# PoE.net
KiCad netlist of a schematic drawn in Altium Designer
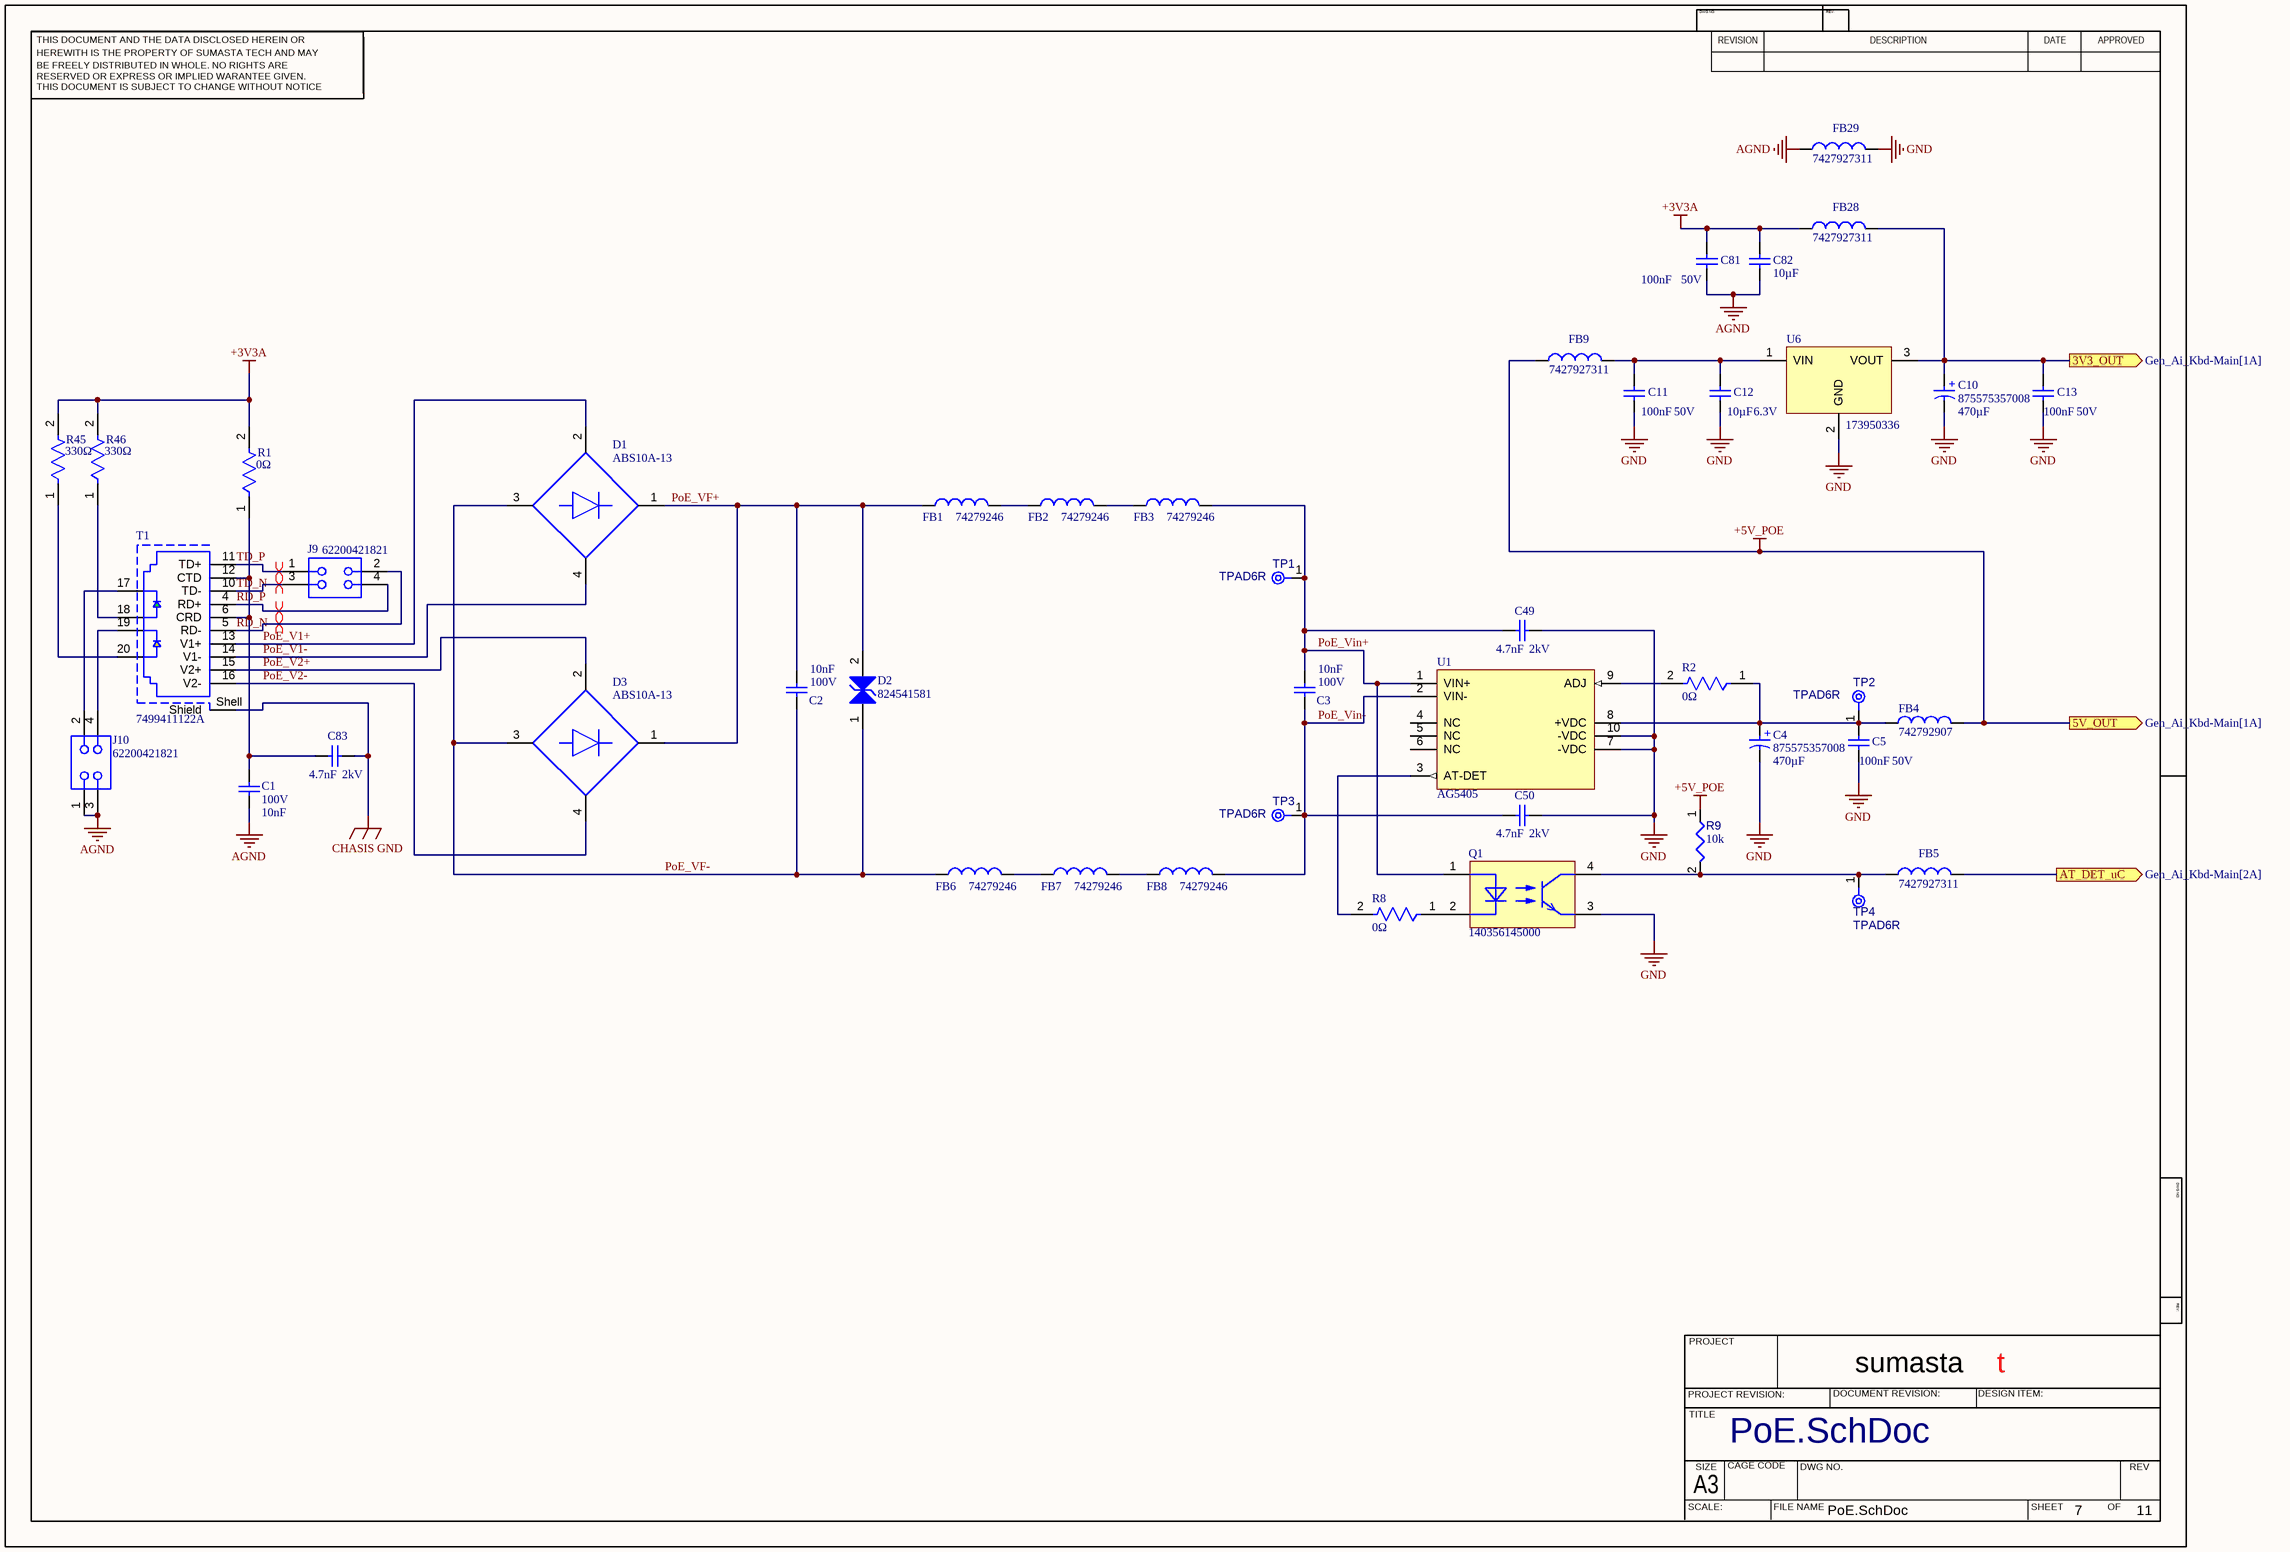
[diagram p0: PoE.SchDoc]

(export (version "E")
  (design (tool "Eeschema 10.0.6"))
  (components
    (comp (ref "C1")
      (value "885012206114")
      (footprint "WCAP-CSGP_0603_L1.6W0.8H0.8_Reflow")
      (description "WCAP-CSGP Multilayer Ceramic Chip Capacitor, General Purpose, size 0603, X7R, 10nF, 100VDC")
      (fields
        (field (name "RATED VOLTAGE (DC)") "100V")
        (field (name "CAPACITANCE") "10nF")
        (field (name "MANUFACTURER") "Wurth Elektronik")
      )
      (libsource (lib "Test365") (part "885012209047R"))
    )
    (comp (ref "C2")
      (value "885012008079")
      (footprint "WCAP-CSGP_1206_L3.2W1.6H1.25")
      (description "WCAP-CSGP Multilayer Ceramic Chip Capacitor, General Purpose, size 1206, NP0, 10nF, 100VDC")
      (fields
        (field (name "RATED VOLTAGE (DC)") "100V")
        (field (name "CAPACITANCE") "10nF")
        (field (name "MANUFACTURER") "Wurth Elektronik")
      )
      (libsource (lib "Test365") (part "885012209047R"))
    )
    (comp (ref "C3")
      (value "885012008079")
      (footprint "WCAP-CSGP_1206_L3.2W1.6H1.25")
      (description "WCAP-CSGP Multilayer Ceramic Chip Capacitor, General Purpose, size 1206, NP0, 10nF, 100VDC")
      (fields
        (field (name "RATED VOLTAGE (DC)") "100V")
        (field (name "CAPACITANCE") "10nF")
        (field (name "MANUFACTURER") "Wurth Elektronik")
      )
      (libsource (lib "Test365") (part "885012209047R"))
    )
    (comp (ref "C4")
      (value "875575357008")
      (footprint "WCAP-HSG5_D10H10.5")
      (description "875575357008 Cap, 470Uf, 16V, Alu Elec, Hybrid, Smd Rohs Compliant: Yes")
      (fields (field (name "CAPACITANCE") "470µF"))
      (libsource (lib "Altium Content Vault") (part "Capacitor_Polarized"))
    )
    (comp (ref "C5")
      (value "885012206095")
      (footprint "WCAP-CSGP_0603_L1.6W0.8H0.8_Reflow")
      (description "WCAP-CSGP Multilayer Ceramic Chip Capacitor, General Purpose, size 0603, X7R, 100nF, 50VDC")
      (fields
        (field (name "CAPACITANCE") "100nF")
        (field (name "MANUFACTURER") "Wurth Elektronik")
        (field (name "RATED VOLTAGE (DC)") "50V")
      )
      (libsource (lib "Test365") (part "885012209047R"))
    )
    (comp (ref "C10")
      (value "875575357008")
      (footprint "WCAP-HSG5_D10H10.5")
      (description "875575357008 Cap, 470Uf, 16V, Alu Elec, Hybrid, Smd Rohs Compliant: Yes")
      (fields (field (name "CAPACITANCE") "470µF"))
      (libsource (lib "Altium Content Vault") (part "Capacitor_Polarized"))
    )
    (comp (ref "C11")
      (value "885012206095")
      (footprint "WCAP-CSGP_0603_L1.6W0.8H0.8_Reflow")
      (description "WCAP-CSGP Multilayer Ceramic Chip Capacitor, General Purpose, size 0603, X7R, 100nF, 50VDC")
      (fields
        (field (name "CAPACITANCE") "100nF")
        (field (name "MANUFACTURER") "Wurth Elektronik")
        (field (name "RATED VOLTAGE (DC)") "50V")
      )
      (libsource (lib "Test365") (part "885012209047R"))
    )
    (comp (ref "C12")
      (value "885012106006")
      (footprint "WCAP-CSGP_0603_L1.6W0.8H0.8_Reflow")
      (description "WCAP-CSGP Multilayer Ceramic Chip Capacitor, General Purpose, size 0603, X5R, 10µF, 6.3VDC")
      (fields
        (field (name "RATED VOLTAGE (DC)") "6.3V")
        (field (name "MANUFACTURER") "Wurth Elektronik")
        (field (name "CAPACITANCE") "10µF")
      )
      (libsource (lib "Test365") (part "885012209047R"))
    )
    (comp (ref "C13")
      (value "885012206095")
      (footprint "WCAP-CSGP_0603_L1.6W0.8H0.8_Reflow")
      (description "WCAP-CSGP Multilayer Ceramic Chip Capacitor, General Purpose, size 0603, X7R, 100nF, 50VDC")
      (fields
        (field (name "CAPACITANCE") "100nF")
        (field (name "MANUFACTURER") "Wurth Elektronik")
        (field (name "RATED VOLTAGE (DC)") "50V")
      )
      (libsource (lib "Test365") (part "885012209047R"))
    )
    (comp (ref "C49")
      (value "885342211008")
      (footprint "WCAP-CSMH_1812_L4.5W3.2H2")
      (description "885342211008 4700PF 2000V X7R 1812 10% - Multilayer Ceramic Capacitors")
      (fields (field (name "VOLTAGE RATING (DC)") "2kV") (field (name "CAPACITANCE") "4.7nF"))
      (libsource (lib "Altium Content Vault") (part "Capacitor_Non-Polarized"))
    )
    (comp (ref "C50")
      (value "885342211008")
      (footprint "WCAP-CSMH_1812_L4.5W3.2H2")
      (description "885342211008 4700PF 2000V X7R 1812 10% - Multilayer Ceramic Capacitors")
      (fields (field (name "VOLTAGE RATING (DC)") "2kV") (field (name "CAPACITANCE") "4.7nF"))
      (libsource (lib "Altium Content Vault") (part "Capacitor_Non-Polarized"))
    )
    (comp (ref "C81")
      (value "885012206095")
      (footprint "WCAP-CSGP_0603_L1.6W0.8H0.8_Reflow")
      (description "WCAP-CSGP Multilayer Ceramic Chip Capacitor, General Purpose, size 0603, X7R, 100nF, 50VDC")
      (fields
        (field (name "CAPACITANCE") "100nF")
        (field (name "MANUFACTURER") "Wurth Elektronik")
        (field (name "RATED VOLTAGE (DC)") "50V")
      )
      (libsource (lib "Test365") (part "885012209047R"))
    )
    (comp (ref "C82")
      (value "885012106006")
      (footprint "WCAP-CSGP_0603_L1.6W0.8H0.8_Reflow")
      (description "WCAP-CSGP Multilayer Ceramic Chip Capacitor, General Purpose, size 0603, X5R, 10µF, 6.3VDC")
      (fields (field (name "MANUFACTURER") "Wurth Elektronik") (field (name "CAPACITANCE") "10µF"))
      (libsource (lib "Test365") (part "885012209047R"))
    )
    (comp (ref "C83")
      (value "885342211008")
      (footprint "WCAP-CSMH_1812_L4.5W3.2H2")
      (description "885342211008 4700PF 2000V X7R 1812 10% - Multilayer Ceramic Capacitors")
      (fields (field (name "VOLTAGE RATING (DC)") "2kV") (field (name "CAPACITANCE") "4.7nF"))
      (libsource (lib "Altium Content Vault") (part "Capacitor_Non-Polarized"))
    )
    (comp (ref "D1")
      (value "ABS10A-13")
      (footprint "FP-SOPA-4-MFG")
      (description "BRIDGE RECT 1PHASE 1KV 1A 4SOPA")
      (libsource (lib "Altium Content Vault") (part "95261e4f58a5ffcdc7f7244183d0b96"))
    )
    (comp (ref "D2")
      (value "824541581")
      (footprint "WE-TVSP_DO-214AB_Bidirectional")
      (description "824541581 TVS diode [Würth Elektronik] 824541581 TVS diode")
      (libsource (lib "Altium Content Vault") (part "WE-TVSP_Bidirectional"))
    )
    (comp (ref "D3")
      (value "ABS10A-13")
      (footprint "FP-SOPA-4-MFG")
      (description "BRIDGE RECT 1PHASE 1KV 1A 4SOPA")
      (libsource (lib "Altium Content Vault") (part "95261e4f58a5ffcdc7f7244183d0b96"))
    )
    (comp (ref "FB1")
      (value "74279246")
      (footprint "WE-CBF_1806_L4.5W1.6H1.6_HS/WB")
      (description "WE-CBF SMT EMI Suppression Ferrite Bead, size 1806, 1000Ohm, 1.5A")
      (fields (field (name "MANUFACTURER") "Wurth Elektronik"))
      (libsource (lib "Test365") (part "7427928801"))
    )
    (comp (ref "FB2")
      (value "74279246")
      (footprint "WE-CBF_1806_L4.5W1.6H1.6_HS/WB")
      (description "WE-CBF SMT EMI Suppression Ferrite Bead, size 1806, 1000Ohm, 1.5A")
      (fields (field (name "MANUFACTURER") "Wurth Elektronik"))
      (libsource (lib "Test365") (part "7427928801"))
    )
    (comp (ref "FB3")
      (value "74279246")
      (footprint "WE-CBF_1806_L4.5W1.6H1.6_HS/WB")
      (description "WE-CBF SMT EMI Suppression Ferrite Bead, size 1806, 1000Ohm, 1.5A")
      (fields (field (name "MANUFACTURER") "Wurth Elektronik"))
      (libsource (lib "Test365") (part "7427928801"))
    )
    (comp (ref "FB4")
      (value "742792907")
      (footprint "WE-PF_1280")
      (fields (field (name "TOLERANCE") "25%"))
      (libsource (lib "Altium Content Vault") (part "Ferrite"))
    )
    (comp (ref "FB5")
      (value "7427927311")
      (footprint "WE-CBF_0402_L1W0.5H0.5_HC")
      (fields (field (name "TOLERANCE") "25%"))
      (libsource (lib "Altium Content Vault") (part "Ferrite"))
    )
    (comp (ref "FB6")
      (value "74279246")
      (footprint "WE-CBF_1806_L4.5W1.6H1.6_HS/WB")
      (description "WE-CBF SMT EMI Suppression Ferrite Bead, size 1806, 1000Ohm, 1.5A")
      (fields (field (name "MANUFACTURER") "Wurth Elektronik"))
      (libsource (lib "Test365") (part "7427928801"))
    )
    (comp (ref "FB7")
      (value "74279246")
      (footprint "WE-CBF_1806_L4.5W1.6H1.6_HS/WB")
      (description "WE-CBF SMT EMI Suppression Ferrite Bead, size 1806, 1000Ohm, 1.5A")
      (fields (field (name "MANUFACTURER") "Wurth Elektronik"))
      (libsource (lib "Test365") (part "7427928801"))
    )
    (comp (ref "FB8")
      (value "74279246")
      (footprint "WE-CBF_1806_L4.5W1.6H1.6_HS/WB")
      (description "WE-CBF SMT EMI Suppression Ferrite Bead, size 1806, 1000Ohm, 1.5A")
      (fields (field (name "MANUFACTURER") "Wurth Elektronik"))
      (libsource (lib "Test365") (part "7427928801"))
    )
    (comp (ref "FB9")
      (value "7427927311")
      (footprint "WE-CBF_0402_L1W0.5H0.5_HC")
      (fields (field (name "TOLERANCE") "25%"))
      (libsource (lib "Altium Content Vault") (part "Ferrite"))
    )
    (comp (ref "FB28")
      (value "7427927311")
      (footprint "WE-CBF_0402_L1W0.5H0.5_HC")
      (fields (field (name "TOLERANCE") "25%"))
      (libsource (lib "Altium Content Vault") (part "Ferrite"))
    )
    (comp (ref "FB29")
      (value "7427927311")
      (footprint "WE-CBF_0402_L1W0.5H0.5_HC")
      (fields (field (name "TOLERANCE") "25%"))
      (libsource (lib "Altium Content Vault") (part "Ferrite"))
    )
    (comp (ref "J9")
      (value "62200421821")
      (footprint "62200421821")
      (libsource (lib "Altium Content Vault") (part "Header_Female_2R_04P"))
    )
    (comp (ref "J10")
      (value "62200421821")
      (footprint "62200421821")
      (libsource (lib "Altium Content Vault") (part "Header_Female_2R_04P"))
    )
    (comp (ref "Q1")
      (value "140356145000")
      (footprint "WL-OCPT_SOP4")
      (description "140356145000 Optocoupler, Transistor, 80V, Sop-4 Rohs Compliant: Yes")
      (libsource (lib "Altium Content Vault") (part "Optocoupler Phototransistor_DC_1 Channel"))
    )
    (comp (ref "R1")
      (value "0Ω")
      (footprint "FP-RC0603-MFG")
      (description "RES SMD 0 OHM JUMPER 1/10W 0603")
      (fields
        (field (name "TOLERANCE") "1%")
        (field (name "OCTOPART") "https://octopart.com/rc0603fr-070rl-yageo-1180803")
      )
      (libsource (lib "Altium Content Vault") (part "1029c3af85768c4190bb7ad29bc67b5"))
    )
    (comp (ref "R2")
      (value "0Ω")
      (footprint "FP-RC0603-MFG")
      (description "RES SMD 0 OHM JUMPER 1/10W 0603")
      (fields
        (field (name "TOLERANCE") "1%")
        (field (name "OCTOPART") "https://octopart.com/rc0603fr-070rl-yageo-1180803")
      )
      (libsource (lib "Altium Content Vault") (part "1029c3af85768c4190bb7ad29bc67b5"))
    )
    (comp (ref "R8")
      (value "0Ω")
      (footprint "FP-RC0603-MFG")
      (description "RES SMD 0 OHM JUMPER 1/10W 0603")
      (fields
        (field (name "TOLERANCE") "1%")
        (field (name "OCTOPART") "https://octopart.com/rc0603fr-070rl-yageo-1180803")
      )
      (libsource (lib "Altium Content Vault") (part "1029c3af85768c4190bb7ad29bc67b5"))
    )
    (comp (ref "R9")
      (value "10k")
      (footprint "RESC1608X55X25ML10T15")
      (description "Chip Resistor, 10 KOhm, +/- 1%, 01 W, -55 to 155 degC, 0603 (1608 Metric)")
      (fields (field (name "POWER") "100mW") (field (name "TOLERANCE") "1%"))
      (libsource (lib "Test365") (part "RES-2"))
    )
    (comp (ref "R45")
      (value "330Ω")
      (footprint "FP-RC0603-MFG")
      (description "RES SMD 0 OHM JUMPER 1/10W 0603")
      (fields
        (field (name "TOLERANCE") "1%")
        (field (name "OCTOPART") "https://octopart.com/rc0603fr-070rl-yageo-1180803")
      )
      (libsource (lib "Altium Content Vault") (part "1029c3af85768c4190bb7ad29bc67b5"))
    )
    (comp (ref "R46")
      (value "330Ω")
      (footprint "FP-RC0603-MFG")
      (description "RES SMD 0 OHM JUMPER 1/10W 0603")
      (fields
        (field (name "TOLERANCE") "1%")
        (field (name "OCTOPART") "https://octopart.com/rc0603fr-070rl-yageo-1180803")
      )
      (libsource (lib "Altium Content Vault") (part "1029c3af85768c4190bb7ad29bc67b5"))
    )
    (comp (ref "T1")
      (value "7499411122A")
      (footprint "7499411122A")
      (description "7499411122A Rj45 Conn, R/A Jack, 8P8C, 1Port, Th Rohs Compliant: Yes")
      (libsource (lib "Altium Content Vault") (part "7499411122A"))
    )
    (comp (ref "TP1")
      (value "TPAD6R")
      (footprint "TP06R")
      (description "0.6mm round")
      (libsource (lib "Test365") (part "CMP-001-0001-4"))
    )
    (comp (ref "TP2")
      (value "TPAD6R")
      (footprint "TP06R")
      (description "0.6mm round")
      (libsource (lib "Test365") (part "CMP-001-0001-4"))
    )
    (comp (ref "TP3")
      (value "TPAD6R")
      (footprint "TP06R")
      (description "0.6mm round")
      (libsource (lib "Test365") (part "CMP-001-0001-4"))
    )
    (comp (ref "TP4")
      (value "TPAD6R")
      (footprint "TP06R")
      (description "0.6mm round")
      (libsource (lib "Test365") (part "CMP-001-0001-4"))
    )
    (comp (ref "U1")
      (value "AG5405")
      (footprint "AG540X")
      (description "PoE Module 802.3at")
      (libsource (lib "Test365") (part "SYM_AG540X"))
    )
    (comp (ref "U6")
      (value "173950336")
      (footprint "WPME-FDSM_SIP-3_L11.6W7.55H10.16")
      (description "173950336 WPME-FDSM Fixed Step Down Regulator Module")
      (libsource (lib "Altium Content Vault") (part "SIP-3_WPME-FDSM"))
    )
  )
  (nets
    (net (code "1") (name "+3V3A") (class "Default")
      (node (ref "C81") (pin "2") (pinfunction "2_2") (pintype "passive"))
      (node (ref "C82") (pin "2") (pinfunction "2_2") (pintype "passive"))
      (node (ref "FB28") (pin "1") (pinfunction "1_1") (pintype "passive"))
      (node (ref "R1") (pin "2") (pinfunction "2_2") (pintype "passive"))
      (node (ref "R45") (pin "2") (pinfunction "2_2") (pintype "passive"))
      (node (ref "R46") (pin "2") (pinfunction "2_2") (pintype "passive"))
    )
    (net (code "2") (name "+5V_POE") (class "Default")
      (node (ref "FB4") (pin "2") (pinfunction "2_2") (pintype "passive"))
      (node (ref "FB9") (pin "1") (pinfunction "1_1") (pintype "passive"))
      (node (ref "R9") (pin "1") (pinfunction "1_1") (pintype "passive"))
    )
    (net (code "3") (name "/3V3_OUT") (class "Default")
      (node (ref "C10") (pin "1") (pinfunction "P_1") (pintype "passive"))
      (node (ref "C13") (pin "2") (pinfunction "2_2") (pintype "passive"))
      (node (ref "FB28") (pin "2") (pinfunction "2_2") (pintype "passive"))
      (node (ref "U6") (pin "3") (pinfunction "VOUT_3") (pintype "passive"))
    )
    (net (code "4") (name "/AT_DET_uC") (class "Default")
      (node (ref "FB5") (pin "2") (pinfunction "2_2") (pintype "passive"))
    )
    (net (code "5") (name "/PoE_V1+") (class "Default")
      (node (ref "D1") (pin "2") (pinfunction "1_~_2") (pintype "passive"))
      (node (ref "T1") (pin "13") (pinfunction "V1+_13") (pintype "passive"))
    )
    (net (code "6") (name "/PoE_V1-") (class "Default")
      (node (ref "D1") (pin "4") (pinfunction "2_~_4") (pintype "passive"))
      (node (ref "T1") (pin "14") (pinfunction "V1-_14") (pintype "passive"))
    )
    (net (code "7") (name "/PoE_V2+") (class "Default")
      (node (ref "D3") (pin "2") (pinfunction "1_~_2") (pintype "passive"))
      (node (ref "T1") (pin "15") (pinfunction "V2+_15") (pintype "passive"))
    )
    (net (code "8") (name "/PoE_V2-") (class "Default")
      (node (ref "D3") (pin "4") (pinfunction "2_~_4") (pintype "passive"))
      (node (ref "T1") (pin "16") (pinfunction "V2-_16") (pintype "passive"))
    )
    (net (code "9") (name "/PoE_VF+") (class "Default")
      (node (ref "C2") (pin "2") (pinfunction "2_2") (pintype "passive"))
      (node (ref "D1") (pin "1") (pinfunction "+_1") (pintype "passive"))
      (node (ref "D2") (pin "2") (pinfunction "2_2") (pintype "passive"))
      (node (ref "D3") (pin "1") (pinfunction "+_1") (pintype "passive"))
      (node (ref "FB1") (pin "1") (pinfunction "1_1") (pintype "passive"))
    )
    (net (code "10") (name "/PoE_VF-") (class "Default")
      (node (ref "C2") (pin "1") (pinfunction "1_1") (pintype "passive"))
      (node (ref "D1") (pin "3") (pinfunction "-_3") (pintype "passive"))
      (node (ref "D2") (pin "1") (pinfunction "1_1") (pintype "passive"))
      (node (ref "D3") (pin "3") (pinfunction "-_3") (pintype "passive"))
      (node (ref "FB6") (pin "1") (pinfunction "1_1") (pintype "passive"))
    )
    (net (code "11") (name "/PoE_Vin+") (class "Default")
      (node (ref "C3") (pin "2") (pinfunction "2_2") (pintype "passive"))
      (node (ref "C49") (pin "1") (pinfunction "1_1") (pintype "passive"))
      (node (ref "FB3") (pin "2") (pinfunction "2_2") (pintype "passive"))
      (node (ref "Q1") (pin "1") (pinfunction "Anode_1") (pintype "passive"))
      (node (ref "TP1") (pin "1") (pinfunction "TP_1") (pintype "passive"))
      (node (ref "U1") (pin "1") (pinfunction "VIN+_1") (pintype "power_in"))
    )
    (net (code "12") (name "/PoE_Vin-") (class "Default")
      (node (ref "C3") (pin "1") (pinfunction "1_1") (pintype "passive"))
      (node (ref "C50") (pin "1") (pinfunction "1_1") (pintype "passive"))
      (node (ref "FB8") (pin "2") (pinfunction "2_2") (pintype "passive"))
      (node (ref "TP3") (pin "1") (pinfunction "TP_1") (pintype "passive"))
      (node (ref "U1") (pin "2") (pinfunction "VIN-_2") (pintype "power_in"))
    )
    (net (code "13") (name "/RD_N") (class "Default")
      (node (ref "J9") (pin "2") (pinfunction "2_2") (pintype "passive"))
      (node (ref "T1") (pin "5") (pinfunction "RD-_5") (pintype "passive"))
    )
    (net (code "14") (name "/RD_P") (class "Default")
      (node (ref "J9") (pin "4") (pinfunction "4_4") (pintype "passive"))
      (node (ref "T1") (pin "4") (pinfunction "RD+_4") (pintype "passive"))
    )
    (net (code "15") (name "/TD_N") (class "Default")
      (node (ref "J9") (pin "3") (pinfunction "3_3") (pintype "passive"))
      (node (ref "T1") (pin "10") (pinfunction "TD-_10") (pintype "passive"))
    )
    (net (code "16") (name "/TD_P") (class "Default")
      (node (ref "J9") (pin "1") (pinfunction "1_1") (pintype "passive"))
      (node (ref "T1") (pin "11") (pinfunction "TD+_11") (pintype "passive"))
    )
    (net (code "17") (name "AGND") (class "Default")
      (node (ref "C1") (pin "2") (pinfunction "2_2") (pintype "passive"))
      (node (ref "C81") (pin "1") (pinfunction "1_1") (pintype "passive"))
      (node (ref "C82") (pin "1") (pinfunction "1_1") (pintype "passive"))
      (node (ref "FB29") (pin "1") (pinfunction "1_1") (pintype "passive"))
      (node (ref "J10") (pin "1") (pinfunction "1_1") (pintype "passive"))
      (node (ref "J10") (pin "3") (pinfunction "3_3") (pintype "passive"))
    )
    (net (code "18") (name "CHASIS GND") (class "Default")
      (node (ref "C83") (pin "2") (pinfunction "2_2") (pintype "passive"))
      (node (ref "T1") (pin "Shell") (pinfunction "Shield_Shell") (pintype "passive"))
    )
    (net (code "19") (name "GND") (class "Default")
      (node (ref "C10") (pin "2") (pinfunction "N_2") (pintype "passive"))
      (node (ref "C11") (pin "1") (pinfunction "1_1") (pintype "passive"))
      (node (ref "C12") (pin "1") (pinfunction "1_1") (pintype "passive"))
      (node (ref "C13") (pin "1") (pinfunction "1_1") (pintype "passive"))
      (node (ref "C4") (pin "2") (pinfunction "N_2") (pintype "passive"))
      (node (ref "C49") (pin "2") (pinfunction "2_2") (pintype "passive"))
      (node (ref "C5") (pin "1") (pinfunction "1_1") (pintype "passive"))
      (node (ref "C50") (pin "2") (pinfunction "2_2") (pintype "passive"))
      (node (ref "FB29") (pin "2") (pinfunction "2_2") (pintype "passive"))
      (node (ref "Q1") (pin "3") (pinfunction "Emitter_3") (pintype "passive"))
      (node (ref "U1") (pin "10") (pinfunction "-VDC_10") (pintype "power_in"))
      (node (ref "U1") (pin "7") (pinfunction "-VDC_7") (pintype "power_in"))
      (node (ref "U6") (pin "2") (pinfunction "GND_2") (pintype "passive"))
    )
    (net (code "20") (name "Net-(C4-P)") (class "Default")
      (node (ref "C4") (pin "1") (pinfunction "P_1") (pintype "passive"))
      (node (ref "C5") (pin "2") (pinfunction "2_2") (pintype "passive"))
      (node (ref "FB4") (pin "1") (pinfunction "1_1") (pintype "passive"))
      (node (ref "R2") (pin "1") (pinfunction "1_1") (pintype "passive"))
      (node (ref "TP2") (pin "1") (pinfunction "TP_1") (pintype "passive"))
      (node (ref "U1") (pin "8") (pinfunction "+VDC_8") (pintype "power_in"))
    )
    (net (code "21") (name "Net-(FB1-Pad2)") (class "Default")
      (node (ref "FB1") (pin "2") (pinfunction "2_2") (pintype "passive"))
      (node (ref "FB2") (pin "1") (pinfunction "1_1") (pintype "passive"))
    )
    (net (code "22") (name "Net-(FB2-Pad2)") (class "Default")
      (node (ref "FB2") (pin "2") (pinfunction "2_2") (pintype "passive"))
      (node (ref "FB3") (pin "1") (pinfunction "1_1") (pintype "passive"))
    )
    (net (code "23") (name "Net-(FB6-Pad2)") (class "Default")
      (node (ref "FB6") (pin "2") (pinfunction "2_2") (pintype "passive"))
      (node (ref "FB7") (pin "1") (pinfunction "1_1") (pintype "passive"))
    )
    (net (code "24") (name "Net-(FB7-Pad2)") (class "Default")
      (node (ref "FB7") (pin "2") (pinfunction "2_2") (pintype "passive"))
      (node (ref "FB8") (pin "1") (pinfunction "1_1") (pintype "passive"))
    )
    (net (code "25") (name "Net-(J10-Pad2)") (class "Default")
      (node (ref "J10") (pin "2") (pinfunction "2_2") (pintype "passive"))
      (node (ref "T1") (pin "17") (pinfunction "17_17") (pintype "passive"))
    )
    (net (code "26") (name "Net-(J10-Pad4)") (class "Default")
      (node (ref "J10") (pin "4") (pinfunction "4_4") (pintype "passive"))
      (node (ref "T1") (pin "19") (pinfunction "19_19") (pintype "passive"))
    )
    (net (code "27") (name "Net-(Q1-Cathode)") (class "Default")
      (node (ref "Q1") (pin "2") (pinfunction "Cathode_2") (pintype "passive"))
      (node (ref "R8") (pin "1") (pinfunction "1_1") (pintype "passive"))
    )
    (net (code "28") (name "Net-(Q1-Collector)") (class "Default")
      (node (ref "FB5") (pin "1") (pinfunction "1_1") (pintype "passive"))
      (node (ref "Q1") (pin "4") (pinfunction "Collector_4") (pintype "passive"))
      (node (ref "R9") (pin "2") (pinfunction "2_2") (pintype "passive"))
      (node (ref "TP4") (pin "1") (pinfunction "TP_1") (pintype "passive"))
    )
    (net (code "29") (name "Net-(R45-Pad1)") (class "Default")
      (node (ref "R45") (pin "1") (pinfunction "1_1") (pintype "passive"))
      (node (ref "T1") (pin "20") (pinfunction "20_20") (pintype "passive"))
    )
    (net (code "30") (name "Net-(R46-Pad1)") (class "Default")
      (node (ref "R46") (pin "1") (pinfunction "1_1") (pintype "passive"))
      (node (ref "T1") (pin "18") (pinfunction "18_18") (pintype "passive"))
    )
    (net (code "31") (name "Net-(T1-CRD)") (class "Default")
      (node (ref "C1") (pin "1") (pinfunction "1_1") (pintype "passive"))
      (node (ref "C83") (pin "1") (pinfunction "1_1") (pintype "passive"))
      (node (ref "R1") (pin "1") (pinfunction "1_1") (pintype "passive"))
      (node (ref "T1") (pin "12") (pinfunction "CTD_12") (pintype "passive"))
      (node (ref "T1") (pin "6") (pinfunction "CRD_6") (pintype "passive"))
    )
    (net (code "32") (name "Net-(U1-ADJ)") (class "Default")
      (node (ref "R2") (pin "2") (pinfunction "2_2") (pintype "passive"))
      (node (ref "U1") (pin "9") (pinfunction "ADJ_9") (pintype "input"))
    )
    (net (code "33") (name "Net-(U1-AT-DET)") (class "Default")
      (node (ref "R8") (pin "2") (pinfunction "2_2") (pintype "passive"))
      (node (ref "U1") (pin "3") (pinfunction "AT-DET_3") (pintype "output"))
    )
    (net (code "34") (name "Net-(U6-VIN)") (class "Default")
      (node (ref "C11") (pin "2") (pinfunction "2_2") (pintype "passive"))
      (node (ref "C12") (pin "2") (pinfunction "2_2") (pintype "passive"))
      (node (ref "FB9") (pin "2") (pinfunction "2_2") (pintype "passive"))
      (node (ref "U6") (pin "1") (pinfunction "VIN_1") (pintype "passive"))
    )
    (net (code "35") (name "unconnected-(U1-NC-Pad4)") (class "Default")
      (node (ref "U1") (pin "4") (pinfunction "NC_4") (pintype "passive"))
    )
    (net (code "36") (name "unconnected-(U1-NC-Pad5)") (class "Default")
      (node (ref "U1") (pin "5") (pinfunction "NC_5") (pintype "passive"))
    )
    (net (code "37") (name "unconnected-(U1-NC-Pad6)") (class "Default")
      (node (ref "U1") (pin "6") (pinfunction "NC_6") (pintype "passive"))
    )
  )
)
